# Power-Supplies.net
KiCad netlist of a schematic drawn in Altium Designer
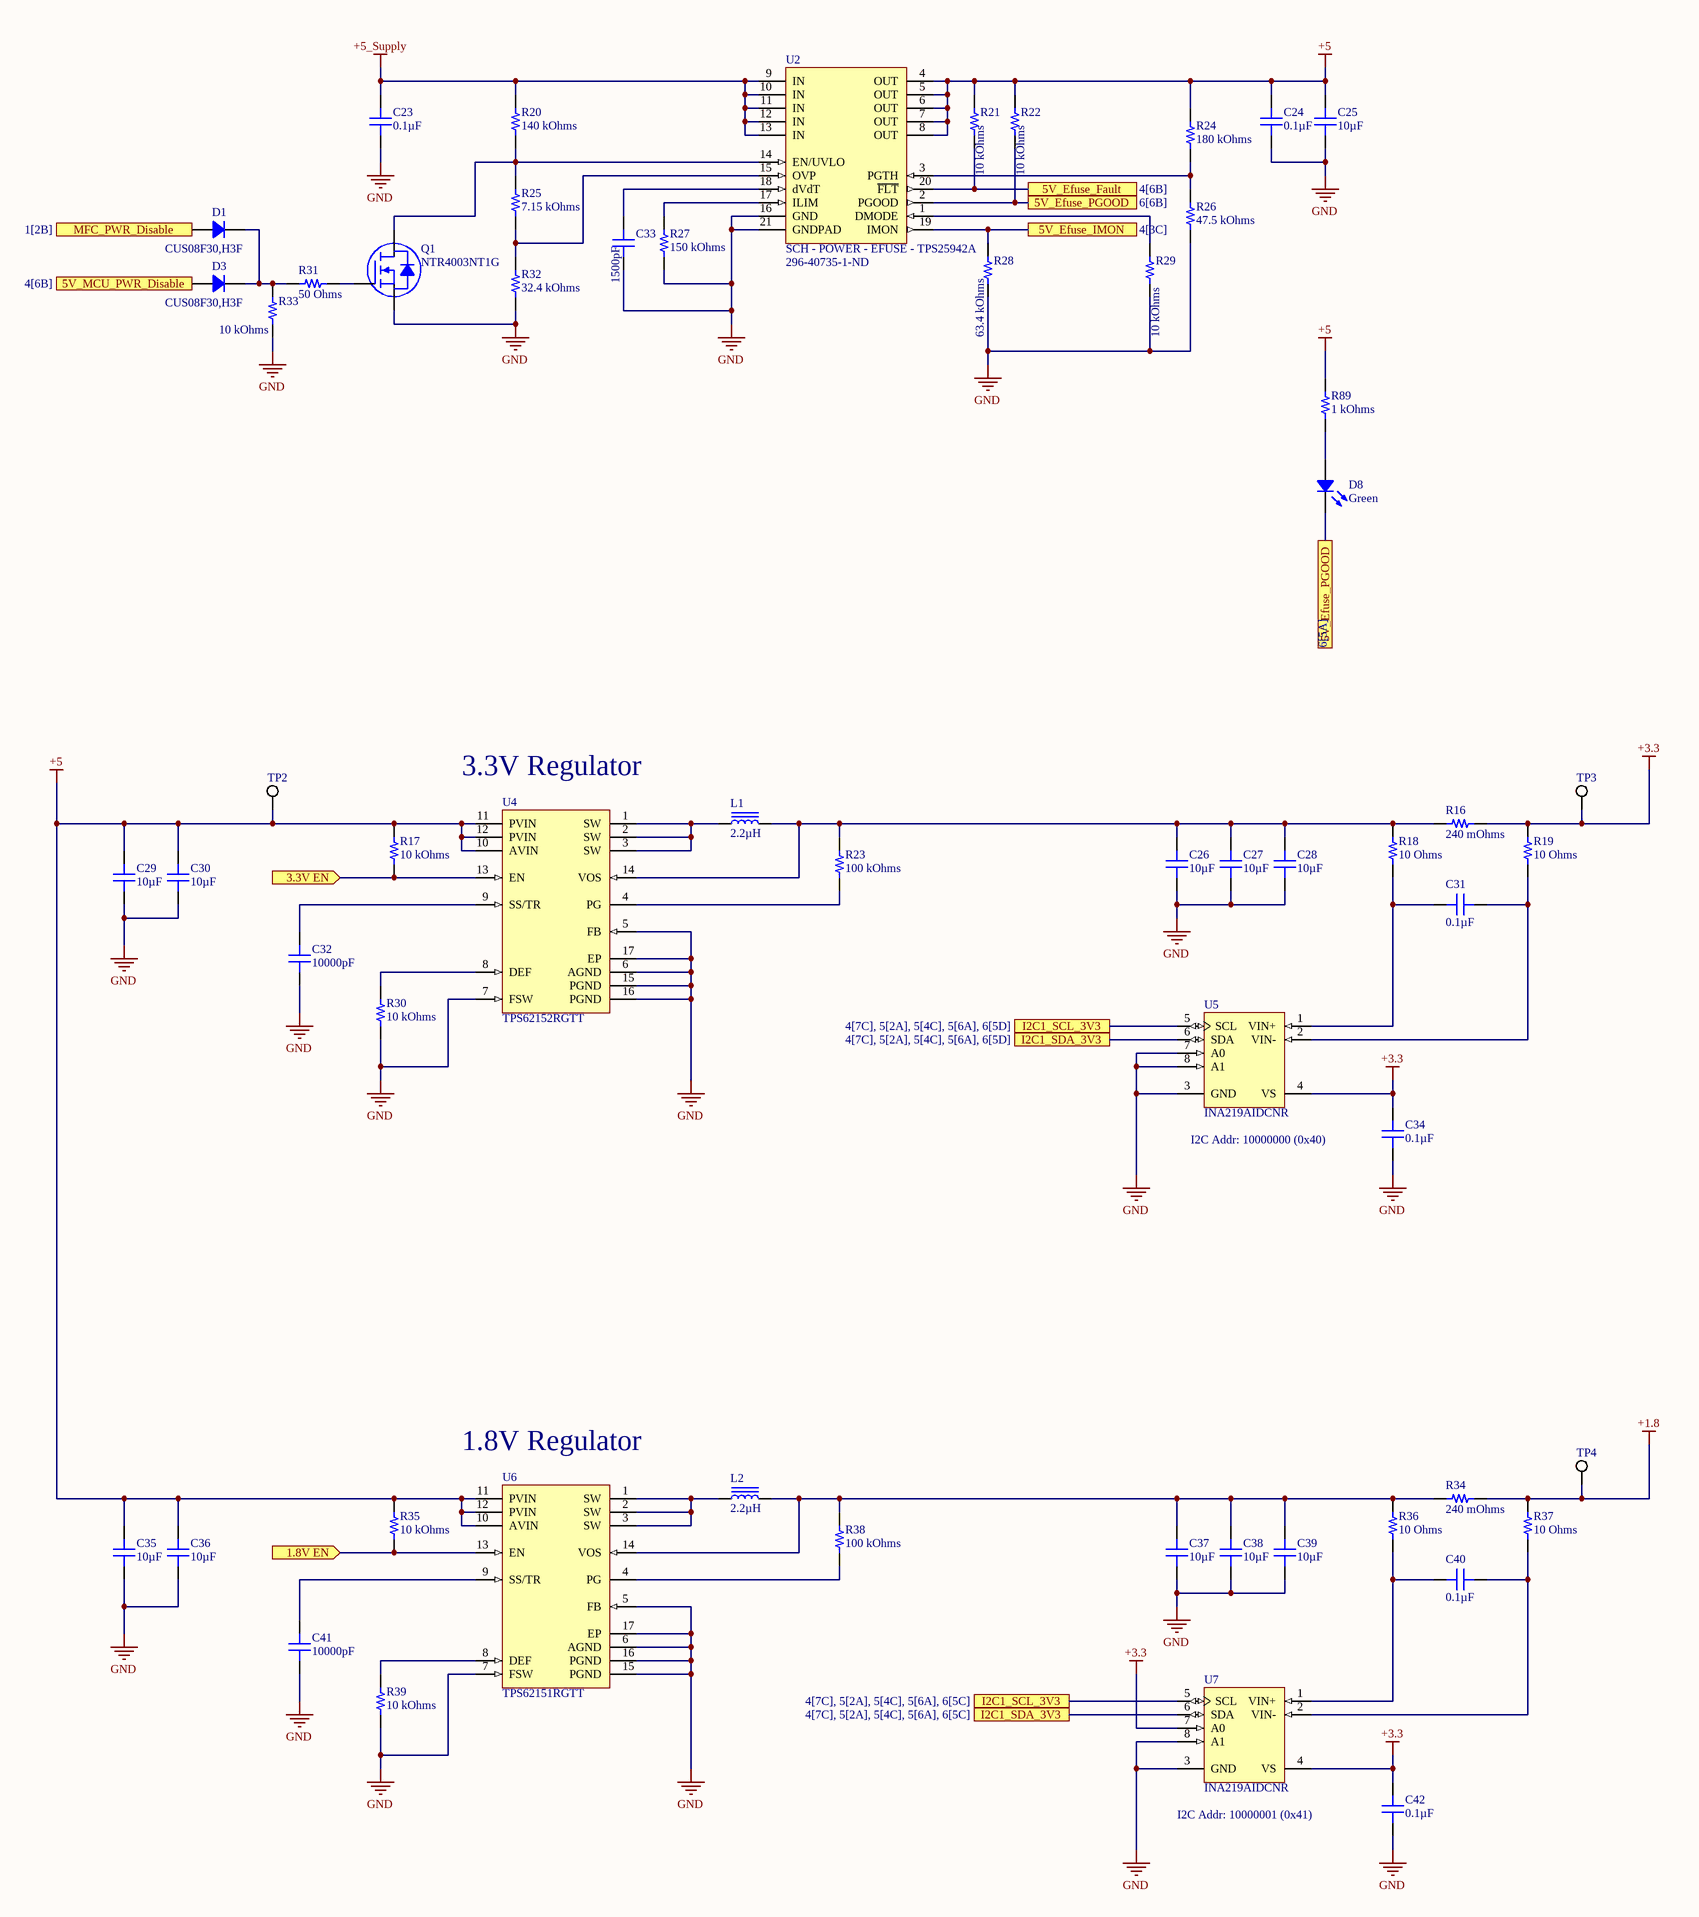
[diagram p0: Power-Supplies.SchDoc]

(export (version "E")
  (design (tool "Eeschema 10.0.6"))
  (components
    (comp (ref "C23")
      (value "0.1µF")
      (footprint "CAP 0603_1608")
      (description "CAP CER 0.1UF 25V X7R 0603")
      (fields
        (field (name "PART NUMBER") "CL10B104KA8WPNC")
        (field (name "MANUFACTURER") "Samsung Electro-Mechanics")
      )
      (libsource (lib "Celestial Altium Library - altium_library") (part "Capacitor"))
    )
    (comp (ref "C24")
      (value "0.1µF")
      (footprint "CAP 0603_1608")
      (description "CAP CER 0.1UF 25V X7R 0603")
      (fields
        (field (name "PART NUMBER") "CL10B104KA8WPNC")
        (field (name "MANUFACTURER") "Samsung Electro-Mechanics")
      )
      (libsource (lib "Celestial Altium Library - altium_library") (part "Capacitor"))
    )
    (comp (ref "C25")
      (value "10µF")
      (footprint "CAP 0805_2012")
      (description "CAP CER 10UF 16V X5R 0805")
      (fields (field (name "PART NUMBER") "CC0805KKX5R7BB106") (field (name "MANUFACTURER") "Yageo"))
      (libsource (lib "Celestial Altium Library - altium_library") (part "Capacitor"))
    )
    (comp (ref "C26")
      (value "10µF")
      (footprint "CAP 0805_2012")
      (description "CAP CER 10UF 16V X5R 0805")
      (fields (field (name "PART NUMBER") "CC0805KKX5R7BB106") (field (name "MANUFACTURER") "Yageo"))
      (libsource (lib "Celestial Altium Library - altium_library") (part "Capacitor"))
    )
    (comp (ref "C27")
      (value "10µF")
      (footprint "CAP 0805_2012")
      (description "CAP CER 10UF 16V X5R 0805")
      (fields (field (name "PART NUMBER") "CC0805KKX5R7BB106") (field (name "MANUFACTURER") "Yageo"))
      (libsource (lib "Celestial Altium Library - altium_library") (part "Capacitor"))
    )
    (comp (ref "C28")
      (value "10µF")
      (footprint "CAP 0805_2012")
      (description "CAP CER 10UF 16V X5R 0805")
      (fields (field (name "PART NUMBER") "CC0805KKX5R7BB106") (field (name "MANUFACTURER") "Yageo"))
      (libsource (lib "Celestial Altium Library - altium_library") (part "Capacitor"))
    )
    (comp (ref "C29")
      (value "10µF")
      (footprint "CAP 0805_2012")
      (description "CAP CER 10UF 16V X5R 0805")
      (fields (field (name "PART NUMBER") "CC0805KKX5R7BB106") (field (name "MANUFACTURER") "Yageo"))
      (libsource (lib "Celestial Altium Library - altium_library") (part "Capacitor"))
    )
    (comp (ref "C30")
      (value "10µF")
      (footprint "CAP 0805_2012")
      (description "CAP CER 10UF 16V X5R 0805")
      (fields (field (name "PART NUMBER") "CC0805KKX5R7BB106") (field (name "MANUFACTURER") "Yageo"))
      (libsource (lib "Celestial Altium Library - altium_library") (part "Capacitor"))
    )
    (comp (ref "C31")
      (value "0.1µF")
      (footprint "CAP 0603_1608")
      (description "CAP CER 0.1UF 25V X7R 0603")
      (fields
        (field (name "PART NUMBER") "CL10B104KA8WPNC")
        (field (name "MANUFACTURER") "Samsung Electro-Mechanics")
      )
      (libsource (lib "Celestial Altium Library - altium_library") (part "Capacitor"))
    )
    (comp (ref "C32")
      (value "10000pF")
      (footprint "CAP 0603_1608")
      (description "CAP CER 10000PF 16V X7R 0603")
      (fields (field (name "PART NUMBER") "C0603S103K4RACTU") (field (name "MANUFACTURER") "KEMET"))
      (libsource (lib "Celestial Altium Library - altium_library") (part "Capacitor"))
    )
    (comp (ref "C33")
      (value "1500pF")
      (footprint "CAP 0603_1608")
      (description "CAP CER 1500PF 25V X7R 0603")
      (fields (field (name "PART NUMBER") "CC0603JRX7R8BB152") (field (name "MANUFACTURER") "Yageo"))
      (libsource (lib "Celestial Altium Library - altium_library") (part "Capacitor"))
    )
    (comp (ref "C34")
      (value "0.1µF")
      (footprint "CAP 0603_1608")
      (description "CAP CER 0.1UF 25V X7R 0603")
      (fields
        (field (name "PART NUMBER") "CL10B104KA8WPNC")
        (field (name "MANUFACTURER") "Samsung Electro-Mechanics")
      )
      (libsource (lib "Celestial Altium Library - altium_library") (part "Capacitor"))
    )
    (comp (ref "C35")
      (value "10µF")
      (footprint "CAP 0805_2012")
      (description "CAP CER 10UF 16V X5R 0805")
      (fields (field (name "PART NUMBER") "CC0805KKX5R7BB106") (field (name "MANUFACTURER") "Yageo"))
      (libsource (lib "Celestial Altium Library - altium_library") (part "Capacitor"))
    )
    (comp (ref "C36")
      (value "10µF")
      (footprint "CAP 0805_2012")
      (description "CAP CER 10UF 16V X5R 0805")
      (fields (field (name "PART NUMBER") "CC0805KKX5R7BB106") (field (name "MANUFACTURER") "Yageo"))
      (libsource (lib "Celestial Altium Library - altium_library") (part "Capacitor"))
    )
    (comp (ref "C37")
      (value "10µF")
      (footprint "CAP 0805_2012")
      (description "CAP CER 10UF 16V X5R 0805")
      (fields (field (name "PART NUMBER") "CC0805KKX5R7BB106") (field (name "MANUFACTURER") "Yageo"))
      (libsource (lib "Celestial Altium Library - altium_library") (part "Capacitor"))
    )
    (comp (ref "C38")
      (value "10µF")
      (footprint "CAP 0805_2012")
      (description "CAP CER 10UF 16V X5R 0805")
      (fields (field (name "PART NUMBER") "CC0805KKX5R7BB106") (field (name "MANUFACTURER") "Yageo"))
      (libsource (lib "Celestial Altium Library - altium_library") (part "Capacitor"))
    )
    (comp (ref "C39")
      (value "10µF")
      (footprint "CAP 0805_2012")
      (description "CAP CER 10UF 16V X5R 0805")
      (fields (field (name "PART NUMBER") "CC0805KKX5R7BB106") (field (name "MANUFACTURER") "Yageo"))
      (libsource (lib "Celestial Altium Library - altium_library") (part "Capacitor"))
    )
    (comp (ref "C40")
      (value "0.1µF")
      (footprint "CAP 0603_1608")
      (description "CAP CER 0.1UF 25V X7R 0603")
      (fields
        (field (name "PART NUMBER") "CL10B104KA8WPNC")
        (field (name "MANUFACTURER") "Samsung Electro-Mechanics")
      )
      (libsource (lib "Celestial Altium Library - altium_library") (part "Capacitor"))
    )
    (comp (ref "C41")
      (value "10000pF")
      (footprint "CAP 0603_1608")
      (description "CAP CER 10000PF 16V X7R 0603")
      (fields (field (name "PART NUMBER") "C0603S103K4RACTU") (field (name "MANUFACTURER") "KEMET"))
      (libsource (lib "Celestial Altium Library - altium_library") (part "Capacitor"))
    )
    (comp (ref "C42")
      (value "0.1µF")
      (footprint "CAP 0603_1608")
      (description "CAP CER 0.1UF 25V X7R 0603")
      (fields
        (field (name "PART NUMBER") "CL10B104KA8WPNC")
        (field (name "MANUFACTURER") "Samsung Electro-Mechanics")
      )
      (libsource (lib "Celestial Altium Library - altium_library") (part "Capacitor"))
    )
    (comp (ref "D1")
      (value "CUS08F30,H3F")
      (footprint "SOD323")
      (description "DIODE SCHOTTKY 30V 800MA USC")
      (fields (field (name "MANUFACTURER") "Toshiba Semiconductor and Storage"))
      (libsource (lib "Celestial Altium Library - altium_library") (part "Diode"))
    )
    (comp (ref "D3")
      (value "CUS08F30,H3F")
      (footprint "SOD323")
      (description "DIODE SCHOTTKY 30V 800MA USC")
      (fields (field (name "MANUFACTURER") "Toshiba Semiconductor and Storage"))
      (libsource (lib "Celestial Altium Library - altium_library") (part "Diode"))
    )
    (comp (ref "D8")
      (value "Green")
      (footprint "LED 0603_1608 GREEN")
      (description "LED GREEN CLEAR CHIP SMD")
      (fields (field (name "PART NUMBER") "LTST-C193KGKT-5A") (field (name "MANUFACTURER") "Lite-On Inc."))
      (libsource (lib "Celestial Altium Library - altium_library") (part "LED"))
    )
    (comp (ref "L1")
      (value "2.2µH")
      (footprint "BOURNS SRN4018")
      (description "FIXED IND 2.2UH 2.9A 44 MOHM SMD")
      (fields (field (name "PART NUMBER") "SRN4018-2R2M") (field (name "MANUFACTURER") "Bourns Inc."))
      (libsource (lib "Celestial Altium Library - altium_library") (part "Inductor"))
    )
    (comp (ref "L2")
      (value "2.2µH")
      (footprint "BOURNS SRN4018")
      (description "FIXED IND 2.2UH 2.9A 44 MOHM SMD")
      (fields (field (name "PART NUMBER") "SRN4018-2R2M") (field (name "MANUFACTURER") "Bourns Inc."))
      (libsource (lib "Celestial Altium Library - altium_library") (part "Inductor"))
    )
    (comp (ref "Q1")
      (value "NTR4003NT1G")
      (footprint "ON SEMI SOT-23-3")
      (description "MOSFET N-CH 30V 500MA SOT-23")
      (fields (field (name "MANUFACTURER") "ON Semiconductor"))
      (libsource (lib "Celestial Altium Library - altium_library") (part "ON SEMI MOSFET N-CH SOT-23-3"))
    )
    (comp (ref "R16")
      (value "240 mOhms")
      (footprint "RES 0805_2012")
      (description "RES 0.24 OHM 1% 1/2W 0805")
      (fields
        (field (name "PART NUMBER") "ERJ-6DQFR24V")
        (field (name "MANUFACTURER") "Panasonic Electronic Components")
      )
      (libsource (lib "Celestial Altium Library - altium_library") (part "Resistor"))
    )
    (comp (ref "R17")
      (value "10 kOhms")
      (footprint "RES 0603_1608")
      (description "RES 10K OHM 5% 1/10W 0603")
      (fields
        (field (name "PART NUMBER") "RMCF0603JT10K0")
        (field (name "MANUFACTURER") "Stackpole Electronics Inc")
      )
      (libsource (lib "Celestial Altium Library - altium_library") (part "Resistor"))
    )
    (comp (ref "R18")
      (value "10 Ohms")
      (footprint "RES 0603_1608")
      (description "CRGCQ 0603 10R 1%")
      (fields
        (field (name "PART NUMBER") "CRGCQ0603F10R")
        (field (name "MANUFACTURER") "TE Connectivity Passive Product")
      )
      (libsource (lib "Celestial Altium Library - altium_library") (part "Resistor"))
    )
    (comp (ref "R19")
      (value "10 Ohms")
      (footprint "RES 0603_1608")
      (description "CRGCQ 0603 10R 1%")
      (fields
        (field (name "PART NUMBER") "CRGCQ0603F10R")
        (field (name "MANUFACTURER") "TE Connectivity Passive Product")
      )
      (libsource (lib "Celestial Altium Library - altium_library") (part "Resistor"))
    )
    (comp (ref "R20")
      (value "140 kOhms")
      (footprint "RES 0603_1608")
      (description "RES SMD 140K OHM 0.1% 1/10W 0603")
      (fields (field (name "PART NUMBER") "RT0603BRE07140KL") (field (name "MANUFACTURER") "Yageo"))
      (libsource (lib "Celestial Altium Library - altium_library") (part "Resistor"))
    )
    (comp (ref "R21")
      (value "10 kOhms")
      (footprint "RES 0603_1608")
      (description "RES 10K OHM 5% 1/10W 0603")
      (fields
        (field (name "PART NUMBER") "RMCF0603JT10K0")
        (field (name "MANUFACTURER") "Stackpole Electronics Inc")
      )
      (libsource (lib "Celestial Altium Library - altium_library") (part "Resistor"))
    )
    (comp (ref "R22")
      (value "10 kOhms")
      (footprint "RES 0603_1608")
      (description "RES 10K OHM 5% 1/10W 0603")
      (fields
        (field (name "PART NUMBER") "RMCF0603JT10K0")
        (field (name "MANUFACTURER") "Stackpole Electronics Inc")
      )
      (libsource (lib "Celestial Altium Library - altium_library") (part "Resistor"))
    )
    (comp (ref "R23")
      (value "100 kOhms")
      (footprint "RES 0603_1608")
      (description "RES SMD 100K OHM 5% 1/10W 0603")
      (fields (field (name "PART NUMBER") "RC0603JR-10100KL") (field (name "MANUFACTURER") "Yageo"))
      (libsource (lib "Celestial Altium Library - altium_library") (part "Resistor"))
    )
    (comp (ref "R24")
      (value "180 kOhms")
      (footprint "RES 0603_1608")
      (description "RES 180K OHM 1% 1/10W 0603")
      (fields
        (field (name "PART NUMBER") "RMCF0603FT180K")
        (field (name "MANUFACTURER") "Stackpole Electronics Inc")
      )
      (libsource (lib "Celestial Altium Library - altium_library") (part "Resistor"))
    )
    (comp (ref "R25")
      (value "7.15 kOhms")
      (footprint "RES 0603_1608")
      (description "RES SMD 7.15K OHM 0.1% 1/5W 0603")
      (fields
        (field (name "PART NUMBER") "ERJ-PB3B7151V")
        (field (name "MANUFACTURER") "Panasonic Electronic Components")
      )
      (libsource (lib "Celestial Altium Library - altium_library") (part "Resistor"))
    )
    (comp (ref "R26")
      (value "47.5 kOhms")
      (footprint "RES 0603_1608")
      (description "RES 47.5K OHM 1% 1/10W 0603")
      (fields
        (field (name "PART NUMBER") "RMCF0603FG47K5")
        (field (name "MANUFACTURER") "Stackpole Electronics Inc")
      )
      (libsource (lib "Celestial Altium Library - altium_library") (part "Resistor"))
    )
    (comp (ref "R27")
      (value "150 kOhms")
      (footprint "RES 0603_1608")
      (description "RES 150K OHM 1% 1/10W 0603")
      (fields
        (field (name "PART NUMBER") "RMCF0603FG150K")
        (field (name "MANUFACTURER") "Stackpole Electronics Inc")
      )
      (libsource (lib "Celestial Altium Library - altium_library") (part "Resistor"))
    )
    (comp (ref "R28")
      (value "63.4 kOhms")
      (footprint "RES 0603_1608")
      (description "RES 63.4K OHM 1% 1/10W 0603")
      (fields
        (field (name "PART NUMBER") "RMCF0603FT63K4")
        (field (name "MANUFACTURER") "Stackpole Electronics Inc")
      )
      (libsource (lib "Celestial Altium Library - altium_library") (part "Resistor"))
    )
    (comp (ref "R29")
      (value "10 kOhms")
      (footprint "RES 0603_1608")
      (description "RES 10K OHM 5% 1/10W 0603")
      (fields
        (field (name "PART NUMBER") "RMCF0603JT10K0")
        (field (name "MANUFACTURER") "Stackpole Electronics Inc")
      )
      (libsource (lib "Celestial Altium Library - altium_library") (part "Resistor"))
    )
    (comp (ref "R30")
      (value "10 kOhms")
      (footprint "RES 0603_1608")
      (description "RES 10K OHM 5% 1/10W 0603")
      (fields
        (field (name "PART NUMBER") "RMCF0603JT10K0")
        (field (name "MANUFACTURER") "Stackpole Electronics Inc")
      )
      (libsource (lib "Celestial Altium Library - altium_library") (part "Resistor"))
    )
    (comp (ref "R31")
      (value "50 Ohms")
      (footprint "RES 0603_1608")
      (description "RES SMD 50 OHM 1% 1/10W 0603")
      (fields (field (name "PART NUMBER") "CRCW060350R0FKEA") (field (name "MANUFACTURER") "Vishay Dale"))
      (libsource (lib "Celestial Altium Library - altium_library") (part "Resistor"))
    )
    (comp (ref "R32")
      (value "32.4 kOhms")
      (footprint "RES 0603_1608")
      (description "RES SMD 32.4K OHM 0.1% 1/5W 0603")
      (fields
        (field (name "PART NUMBER") "ERJ-PB3B3242V")
        (field (name "MANUFACTURER") "Panasonic Electronic Components")
      )
      (libsource (lib "Celestial Altium Library - altium_library") (part "Resistor"))
    )
    (comp (ref "R33")
      (value "10 kOhms")
      (footprint "RES 0603_1608")
      (description "RES 10K OHM 5% 1/10W 0603")
      (fields
        (field (name "PART NUMBER") "RMCF0603JT10K0")
        (field (name "MANUFACTURER") "Stackpole Electronics Inc")
      )
      (libsource (lib "Celestial Altium Library - altium_library") (part "Resistor"))
    )
    (comp (ref "R34")
      (value "240 mOhms")
      (footprint "RES 0805_2012")
      (description "RES 0.24 OHM 1% 1/2W 0805")
      (fields
        (field (name "PART NUMBER") "ERJ-6DQFR24V")
        (field (name "MANUFACTURER") "Panasonic Electronic Components")
      )
      (libsource (lib "Celestial Altium Library - altium_library") (part "Resistor"))
    )
    (comp (ref "R35")
      (value "10 kOhms")
      (footprint "RES 0603_1608")
      (description "RES 10K OHM 5% 1/10W 0603")
      (fields
        (field (name "PART NUMBER") "RMCF0603JT10K0")
        (field (name "MANUFACTURER") "Stackpole Electronics Inc")
      )
      (libsource (lib "Celestial Altium Library - altium_library") (part "Resistor"))
    )
    (comp (ref "R36")
      (value "10 Ohms")
      (footprint "RES 0603_1608")
      (description "CRGCQ 0603 10R 1%")
      (fields
        (field (name "PART NUMBER") "CRGCQ0603F10R")
        (field (name "MANUFACTURER") "TE Connectivity Passive Product")
      )
      (libsource (lib "Celestial Altium Library - altium_library") (part "Resistor"))
    )
    (comp (ref "R37")
      (value "10 Ohms")
      (footprint "RES 0603_1608")
      (description "CRGCQ 0603 10R 1%")
      (fields
        (field (name "PART NUMBER") "CRGCQ0603F10R")
        (field (name "MANUFACTURER") "TE Connectivity Passive Product")
      )
      (libsource (lib "Celestial Altium Library - altium_library") (part "Resistor"))
    )
    (comp (ref "R38")
      (value "100 kOhms")
      (footprint "RES 0603_1608")
      (description "RES SMD 100K OHM 5% 1/10W 0603")
      (fields (field (name "PART NUMBER") "RC0603JR-10100KL") (field (name "MANUFACTURER") "Yageo"))
      (libsource (lib "Celestial Altium Library - altium_library") (part "Resistor"))
    )
    (comp (ref "R39")
      (value "10 kOhms")
      (footprint "RES 0603_1608")
      (description "RES 10K OHM 5% 1/10W 0603")
      (fields
        (field (name "PART NUMBER") "RMCF0603JT10K0")
        (field (name "MANUFACTURER") "Stackpole Electronics Inc")
      )
      (libsource (lib "Celestial Altium Library - altium_library") (part "Resistor"))
    )
    (comp (ref "R89")
      (value "1 kOhms")
      (footprint "RES 0603_1608")
      (description "RES 1K OHM 1% 1/8W 0603")
      (fields
        (field (name "PART NUMBER") "RNCP0603FTD1K00")
        (field (name "MANUFACTURER") "Stackpole Electronics Inc")
      )
      (libsource (lib "Celestial Altium Library - altium_library") (part "Resistor"))
    )
    (comp (ref "TP2")
      (value "5019")
      (footprint "KSTN-5019_V")
      (description "Test Point, 1 Position SMD, RoHS, Tape and Reel")
      (libsource (lib "Altium Content Vault") (part "TESTPOINT_WHITE"))
    )
    (comp (ref "TP3")
      (value "5019")
      (footprint "KSTN-5019_V")
      (description "Test Point, 1 Position SMD, RoHS, Tape and Reel")
      (libsource (lib "Altium Content Vault") (part "TESTPOINT_WHITE"))
    )
    (comp (ref "TP4")
      (value "5019")
      (footprint "KSTN-5019_V")
      (description "Test Point, 1 Position SMD, RoHS, Tape and Reel")
      (libsource (lib "Altium Content Vault") (part "TESTPOINT_WHITE"))
    )
    (comp (ref "U2")
      (value "SCH - POWER - EFUSE - TPS25942A")
      (footprint "PCB - LEADLESS - QFN - TI 20-WQFN")
      (fields (field (name "SUPPLIER PART NUMBER 1") "296-40735-1-ND"))
      (libsource (lib "HAB_ICs") (part "SCH - POWER - EFUSE - TPS25942A"))
    )
    (comp (ref "U4")
      (value "TPS62152RGTT")
      (footprint "RGT0016C_V")
      (fields (field (name "MANUFACTURER") "Texas Instruments"))
      (libsource (lib "Altium Content Vault") (part "TI-TPS62152RGT16-1700X1700TP"))
    )
    (comp (ref "U5")
      (value "INA219AIDCNR")
      (footprint "DCN0008A_M")
      (fields (field (name "MANUFACTURER") "Texas Instruments"))
      (libsource (lib "Altium Content Vault") (part "TI-INA219DCN8"))
    )
    (comp (ref "U6")
      (value "TPS62151RGTT")
      (footprint "RGT0016C_V")
      (fields (field (name "MANUFACTURER") "Texas Instruments"))
      (libsource (lib "Altium Content Vault") (part "TI-TPS62151RGT16-1700X1700TP"))
    )
    (comp (ref "U7")
      (value "INA219AIDCNR")
      (footprint "DCN0008A_M")
      (fields (field (name "MANUFACTURER") "Texas Instruments"))
      (libsource (lib "Altium Content Vault") (part "TI-INA219DCN8"))
    )
  )
  (nets
    (net (code "1") (name "+1.8") (class "Default")
      (node (ref "R34") (pin "2") (pinfunction "2_2") (pintype "passive"))
      (node (ref "R37") (pin "2") (pinfunction "2_2") (pintype "passive"))
      (node (ref "TP4") (pin "1") (pinfunction "1_1") (pintype "passive"))
    )
    (net (code "2") (name "+3.3") (class "Default")
      (node (ref "C34") (pin "2") (pinfunction "2_2") (pintype "passive"))
      (node (ref "C42") (pin "2") (pinfunction "2_2") (pintype "passive"))
      (node (ref "R16") (pin "2") (pinfunction "2_2") (pintype "passive"))
      (node (ref "R19") (pin "2") (pinfunction "2_2") (pintype "passive"))
      (node (ref "TP3") (pin "1") (pinfunction "1_1") (pintype "passive"))
      (node (ref "U5") (pin "4") (pinfunction "VS_4") (pintype "power_in"))
      (node (ref "U7") (pin "4") (pinfunction "VS_4") (pintype "power_in"))
      (node (ref "U7") (pin "7") (pinfunction "A0_7") (pintype "input"))
    )
    (net (code "3") (name "+5") (class "Default")
      (node (ref "C24") (pin "2") (pinfunction "2_2") (pintype "passive"))
      (node (ref "C25") (pin "2") (pinfunction "2_2") (pintype "passive"))
      (node (ref "C29") (pin "2") (pinfunction "2_2") (pintype "passive"))
      (node (ref "C30") (pin "2") (pinfunction "2_2") (pintype "passive"))
      (node (ref "C35") (pin "2") (pinfunction "2_2") (pintype "passive"))
      (node (ref "C36") (pin "2") (pinfunction "2_2") (pintype "passive"))
      (node (ref "R17") (pin "2") (pinfunction "2_2") (pintype "passive"))
      (node (ref "R21") (pin "2") (pinfunction "2_2") (pintype "passive"))
      (node (ref "R22") (pin "2") (pinfunction "2_2") (pintype "passive"))
      (node (ref "R24") (pin "2") (pinfunction "2_2") (pintype "passive"))
      (node (ref "R35") (pin "2") (pinfunction "2_2") (pintype "passive"))
      (node (ref "R89") (pin "1") (pinfunction "1_1") (pintype "passive"))
      (node (ref "TP2") (pin "1") (pinfunction "1_1") (pintype "passive"))
      (node (ref "U2") (pin "4") (pinfunction "OUT_4") (pintype "power_in"))
      (node (ref "U2") (pin "5") (pinfunction "OUT_5") (pintype "power_in"))
      (node (ref "U2") (pin "6") (pinfunction "OUT_6") (pintype "power_in"))
      (node (ref "U2") (pin "7") (pinfunction "OUT_7") (pintype "power_in"))
      (node (ref "U2") (pin "8") (pinfunction "OUT_8") (pintype "power_in"))
      (node (ref "U4") (pin "10") (pinfunction "AVIN_10") (pintype "power_in"))
      (node (ref "U4") (pin "11") (pinfunction "PVIN_11") (pintype "power_in"))
      (node (ref "U4") (pin "12") (pinfunction "PVIN_12") (pintype "power_in"))
      (node (ref "U6") (pin "10") (pinfunction "AVIN_10") (pintype "power_in"))
      (node (ref "U6") (pin "11") (pinfunction "PVIN_11") (pintype "power_in"))
      (node (ref "U6") (pin "12") (pinfunction "PVIN_12") (pintype "power_in"))
    )
    (net (code "4") (name "+5_Supply") (class "Default")
      (node (ref "C23") (pin "2") (pinfunction "2_2") (pintype "passive"))
      (node (ref "R20") (pin "2") (pinfunction "2_2") (pintype "passive"))
      (node (ref "U2") (pin "10") (pinfunction "IN_10") (pintype "power_in"))
      (node (ref "U2") (pin "11") (pinfunction "IN_11") (pintype "power_in"))
      (node (ref "U2") (pin "12") (pinfunction "IN_12") (pintype "power_in"))
      (node (ref "U2") (pin "13") (pinfunction "IN_13") (pintype "power_in"))
      (node (ref "U2") (pin "9") (pinfunction "IN_9") (pintype "power_in"))
    )
    (net (code "5") (name "/1.8V EN") (class "Default")
      (node (ref "R35") (pin "1") (pinfunction "1_1") (pintype "passive"))
      (node (ref "U6") (pin "13") (pinfunction "EN_13") (pintype "input"))
    )
    (net (code "6") (name "/3.3V EN") (class "Default")
      (node (ref "R17") (pin "1") (pinfunction "1_1") (pintype "passive"))
      (node (ref "U4") (pin "13") (pinfunction "EN_13") (pintype "input"))
    )
    (net (code "7") (name "/5V_Efuse_Fault") (class "Default")
      (node (ref "R21") (pin "1") (pinfunction "1_1") (pintype "passive"))
      (node (ref "U2") (pin "20") (pinfunction "~{FLT}_20") (pintype "output"))
    )
    (net (code "8") (name "/5V_Efuse_IMON") (class "Default")
      (node (ref "R28") (pin "2") (pinfunction "2_2") (pintype "passive"))
      (node (ref "U2") (pin "19") (pinfunction "IMON_19") (pintype "output"))
    )
    (net (code "9") (name "/5V_Efuse_PGOOD") (class "Default")
      (node (ref "D8") (pin "2") (pinfunction "2_2") (pintype "passive"))
      (node (ref "R22") (pin "1") (pinfunction "1_1") (pintype "passive"))
      (node (ref "U2") (pin "2") (pinfunction "PGOOD_2") (pintype "output"))
    )
    (net (code "10") (name "/5V_MCU_PWR_Disable") (class "Default")
      (node (ref "D3") (pin "1") (pinfunction "1_1") (pintype "passive"))
    )
    (net (code "11") (name "/I2C1_SCL_3V3") (class "Default")
      (node (ref "U5") (pin "5") (pinfunction "SCL_5") (pintype "bidirectional"))
      (node (ref "U7") (pin "5") (pinfunction "SCL_5") (pintype "bidirectional"))
    )
    (net (code "12") (name "/I2C1_SDA_3V3") (class "Default")
      (node (ref "U5") (pin "6") (pinfunction "SDA_6") (pintype "bidirectional"))
      (node (ref "U7") (pin "6") (pinfunction "SDA_6") (pintype "bidirectional"))
    )
    (net (code "13") (name "/MFC_PWR_Disable") (class "Default")
      (node (ref "D1") (pin "1") (pinfunction "1_1") (pintype "passive"))
    )
    (net (code "14") (name "GND") (class "Default")
      (node (ref "C23") (pin "1") (pinfunction "1_1") (pintype "passive"))
      (node (ref "C24") (pin "1") (pinfunction "1_1") (pintype "passive"))
      (node (ref "C25") (pin "1") (pinfunction "1_1") (pintype "passive"))
      (node (ref "C26") (pin "1") (pinfunction "1_1") (pintype "passive"))
      (node (ref "C27") (pin "1") (pinfunction "1_1") (pintype "passive"))
      (node (ref "C28") (pin "1") (pinfunction "1_1") (pintype "passive"))
      (node (ref "C29") (pin "1") (pinfunction "1_1") (pintype "passive"))
      (node (ref "C30") (pin "1") (pinfunction "1_1") (pintype "passive"))
      (node (ref "C32") (pin "1") (pinfunction "1_1") (pintype "passive"))
      (node (ref "C33") (pin "1") (pinfunction "1_1") (pintype "passive"))
      (node (ref "C34") (pin "1") (pinfunction "1_1") (pintype "passive"))
      (node (ref "C35") (pin "1") (pinfunction "1_1") (pintype "passive"))
      (node (ref "C36") (pin "1") (pinfunction "1_1") (pintype "passive"))
      (node (ref "C37") (pin "1") (pinfunction "1_1") (pintype "passive"))
      (node (ref "C38") (pin "1") (pinfunction "1_1") (pintype "passive"))
      (node (ref "C39") (pin "1") (pinfunction "1_1") (pintype "passive"))
      (node (ref "C41") (pin "1") (pinfunction "1_1") (pintype "passive"))
      (node (ref "C42") (pin "1") (pinfunction "1_1") (pintype "passive"))
      (node (ref "Q1") (pin "2") (pinfunction "S_2") (pintype "passive"))
      (node (ref "R26") (pin "1") (pinfunction "1_1") (pintype "passive"))
      (node (ref "R27") (pin "1") (pinfunction "1_1") (pintype "passive"))
      (node (ref "R28") (pin "1") (pinfunction "1_1") (pintype "passive"))
      (node (ref "R29") (pin "1") (pinfunction "1_1") (pintype "passive"))
      (node (ref "R30") (pin "1") (pinfunction "1_1") (pintype "passive"))
      (node (ref "R32") (pin "1") (pinfunction "1_1") (pintype "passive"))
      (node (ref "R33") (pin "1") (pinfunction "1_1") (pintype "passive"))
      (node (ref "R39") (pin "1") (pinfunction "1_1") (pintype "passive"))
      (node (ref "U2") (pin "16") (pinfunction "GND_16") (pintype "power_in"))
      (node (ref "U2") (pin "21") (pinfunction "GNDPAD_21") (pintype "power_in"))
      (node (ref "U4") (pin "15") (pinfunction "PGND_15") (pintype "power_in"))
      (node (ref "U4") (pin "16") (pinfunction "PGND_16") (pintype "power_in"))
      (node (ref "U4") (pin "17") (pinfunction "EP_17") (pintype "power_in"))
      (node (ref "U4") (pin "5") (pinfunction "FB_5") (pintype "input"))
      (node (ref "U4") (pin "6") (pinfunction "AGND_6") (pintype "power_in"))
      (node (ref "U4") (pin "7") (pinfunction "FSW_7") (pintype "input"))
      (node (ref "U5") (pin "3") (pinfunction "GND_3") (pintype "power_in"))
      (node (ref "U5") (pin "7") (pinfunction "A0_7") (pintype "input"))
      (node (ref "U5") (pin "8") (pinfunction "A1_8") (pintype "input"))
      (node (ref "U6") (pin "15") (pinfunction "PGND_15") (pintype "power_in"))
      (node (ref "U6") (pin "16") (pinfunction "PGND_16") (pintype "power_in"))
      (node (ref "U6") (pin "17") (pinfunction "EP_17") (pintype "power_in"))
      (node (ref "U6") (pin "5") (pinfunction "FB_5") (pintype "input"))
      (node (ref "U6") (pin "6") (pinfunction "AGND_6") (pintype "power_in"))
      (node (ref "U6") (pin "7") (pinfunction "FSW_7") (pintype "input"))
      (node (ref "U7") (pin "3") (pinfunction "GND_3") (pintype "power_in"))
      (node (ref "U7") (pin "8") (pinfunction "A1_8") (pintype "input"))
    )
    (net (code "15") (name "Net-(D1-Pad2)") (class "Default")
      (node (ref "D1") (pin "2") (pinfunction "2_2") (pintype "passive"))
      (node (ref "D3") (pin "2") (pinfunction "2_2") (pintype "passive"))
      (node (ref "R31") (pin "2") (pinfunction "2_2") (pintype "passive"))
      (node (ref "R33") (pin "2") (pinfunction "2_2") (pintype "passive"))
    )
    (net (code "16") (name "Net-(D8-Pad1)") (class "Default")
      (node (ref "D8") (pin "1") (pinfunction "1_1") (pintype "passive"))
      (node (ref "R89") (pin "2") (pinfunction "2_2") (pintype "passive"))
    )
    (net (code "17") (name "Net-(L1-Pad1)") (class "Default")
      (node (ref "L1") (pin "1") (pinfunction "1_1") (pintype "passive"))
      (node (ref "U4") (pin "1") (pinfunction "SW_1") (pintype "power_in"))
      (node (ref "U4") (pin "2") (pinfunction "SW_2") (pintype "power_in"))
      (node (ref "U4") (pin "3") (pinfunction "SW_3") (pintype "power_in"))
    )
    (net (code "18") (name "Net-(L2-Pad1)") (class "Default")
      (node (ref "L2") (pin "1") (pinfunction "1_1") (pintype "passive"))
      (node (ref "U6") (pin "1") (pinfunction "SW_1") (pintype "power_in"))
      (node (ref "U6") (pin "2") (pinfunction "SW_2") (pintype "power_in"))
      (node (ref "U6") (pin "3") (pinfunction "SW_3") (pintype "power_in"))
    )
    (net (code "19") (name "Net-(Q1-D)") (class "Default")
      (node (ref "Q1") (pin "3") (pinfunction "D_3") (pintype "passive"))
      (node (ref "R20") (pin "1") (pinfunction "1_1") (pintype "passive"))
      (node (ref "R25") (pin "2") (pinfunction "2_2") (pintype "passive"))
      (node (ref "U2") (pin "14") (pinfunction "EN/UVLO_14") (pintype "input"))
    )
    (net (code "20") (name "Net-(Q1-G)") (class "Default")
      (node (ref "Q1") (pin "1") (pinfunction "G_1") (pintype "passive"))
      (node (ref "R31") (pin "1") (pinfunction "1_1") (pintype "passive"))
    )
    (net (code "21") (name "Net-(U2-DMODE)") (class "Default")
      (node (ref "R29") (pin "2") (pinfunction "2_2") (pintype "passive"))
      (node (ref "U2") (pin "1") (pinfunction "DMODE_1") (pintype "input"))
    )
    (net (code "22") (name "Net-(U2-ILIM)") (class "Default")
      (node (ref "R27") (pin "2") (pinfunction "2_2") (pintype "passive"))
      (node (ref "U2") (pin "17") (pinfunction "ILIM_17") (pintype "input"))
    )
    (net (code "23") (name "Net-(U2-OVP)") (class "Default")
      (node (ref "R25") (pin "1") (pinfunction "1_1") (pintype "passive"))
      (node (ref "R32") (pin "2") (pinfunction "2_2") (pintype "passive"))
      (node (ref "U2") (pin "15") (pinfunction "OVP_15") (pintype "input"))
    )
    (net (code "24") (name "Net-(U2-PGTH)") (class "Default")
      (node (ref "R24") (pin "1") (pinfunction "1_1") (pintype "passive"))
      (node (ref "R26") (pin "2") (pinfunction "2_2") (pintype "passive"))
      (node (ref "U2") (pin "3") (pinfunction "PGTH_3") (pintype "input"))
    )
    (net (code "25") (name "Net-(U2-dVdT)") (class "Default")
      (node (ref "C33") (pin "2") (pinfunction "2_2") (pintype "passive"))
      (node (ref "U2") (pin "18") (pinfunction "dVdT_18") (pintype "input"))
    )
    (net (code "26") (name "Net-(U4-DEF)") (class "Default")
      (node (ref "R30") (pin "2") (pinfunction "2_2") (pintype "passive"))
      (node (ref "U4") (pin "8") (pinfunction "DEF_8") (pintype "input"))
    )
    (net (code "27") (name "Net-(U4-PG)") (class "Default")
      (node (ref "R23") (pin "1") (pinfunction "1_1") (pintype "passive"))
      (node (ref "U4") (pin "4") (pinfunction "PG_4") (pintype "tri_state"))
    )
    (net (code "28") (name "Net-(U4-SS{slash}TR)") (class "Default")
      (node (ref "C32") (pin "2") (pinfunction "2_2") (pintype "passive"))
      (node (ref "U4") (pin "9") (pinfunction "SS/TR_9") (pintype "input"))
    )
    (net (code "29") (name "Net-(U4-VOS)") (class "Default")
      (node (ref "C26") (pin "2") (pinfunction "2_2") (pintype "passive"))
      (node (ref "C27") (pin "2") (pinfunction "2_2") (pintype "passive"))
      (node (ref "C28") (pin "2") (pinfunction "2_2") (pintype "passive"))
      (node (ref "L1") (pin "2") (pinfunction "2_2") (pintype "passive"))
      (node (ref "R16") (pin "1") (pinfunction "1_1") (pintype "passive"))
      (node (ref "R18") (pin "2") (pinfunction "2_2") (pintype "passive"))
      (node (ref "R23") (pin "2") (pinfunction "2_2") (pintype "passive"))
      (node (ref "U4") (pin "14") (pinfunction "VOS_14") (pintype "input"))
    )
    (net (code "30") (name "Net-(U5-VIN+)") (class "Default")
      (node (ref "C31") (pin "2") (pinfunction "2_2") (pintype "passive"))
      (node (ref "R18") (pin "1") (pinfunction "1_1") (pintype "passive"))
      (node (ref "U5") (pin "1") (pinfunction "VIN+_1") (pintype "input"))
    )
    (net (code "31") (name "Net-(U5-VIN-)") (class "Default")
      (node (ref "C31") (pin "1") (pinfunction "1_1") (pintype "passive"))
      (node (ref "R19") (pin "1") (pinfunction "1_1") (pintype "passive"))
      (node (ref "U5") (pin "2") (pinfunction "VIN-_2") (pintype "input"))
    )
    (net (code "32") (name "Net-(U6-DEF)") (class "Default")
      (node (ref "R39") (pin "2") (pinfunction "2_2") (pintype "passive"))
      (node (ref "U6") (pin "8") (pinfunction "DEF_8") (pintype "input"))
    )
    (net (code "33") (name "Net-(U6-PG)") (class "Default")
      (node (ref "R38") (pin "1") (pinfunction "1_1") (pintype "passive"))
      (node (ref "U6") (pin "4") (pinfunction "PG_4") (pintype "tri_state"))
    )
    (net (code "34") (name "Net-(U6-SS{slash}TR)") (class "Default")
      (node (ref "C41") (pin "2") (pinfunction "2_2") (pintype "passive"))
      (node (ref "U6") (pin "9") (pinfunction "SS/TR_9") (pintype "input"))
    )
    (net (code "35") (name "Net-(U6-VOS)") (class "Default")
      (node (ref "C37") (pin "2") (pinfunction "2_2") (pintype "passive"))
      (node (ref "C38") (pin "2") (pinfunction "2_2") (pintype "passive"))
      (node (ref "C39") (pin "2") (pinfunction "2_2") (pintype "passive"))
      (node (ref "L2") (pin "2") (pinfunction "2_2") (pintype "passive"))
      (node (ref "R34") (pin "1") (pinfunction "1_1") (pintype "passive"))
      (node (ref "R36") (pin "2") (pinfunction "2_2") (pintype "passive"))
      (node (ref "R38") (pin "2") (pinfunction "2_2") (pintype "passive"))
      (node (ref "U6") (pin "14") (pinfunction "VOS_14") (pintype "input"))
    )
    (net (code "36") (name "Net-(U7-VIN+)") (class "Default")
      (node (ref "C40") (pin "2") (pinfunction "2_2") (pintype "passive"))
      (node (ref "R36") (pin "1") (pinfunction "1_1") (pintype "passive"))
      (node (ref "U7") (pin "1") (pinfunction "VIN+_1") (pintype "input"))
    )
    (net (code "37") (name "Net-(U7-VIN-)") (class "Default")
      (node (ref "C40") (pin "1") (pinfunction "1_1") (pintype "passive"))
      (node (ref "R37") (pin "1") (pinfunction "1_1") (pintype "passive"))
      (node (ref "U7") (pin "2") (pinfunction "VIN-_2") (pintype "input"))
    )
  )
)
